# op-synth_0_9.net
KiCad netlist of a schematic drawn in EAGLE
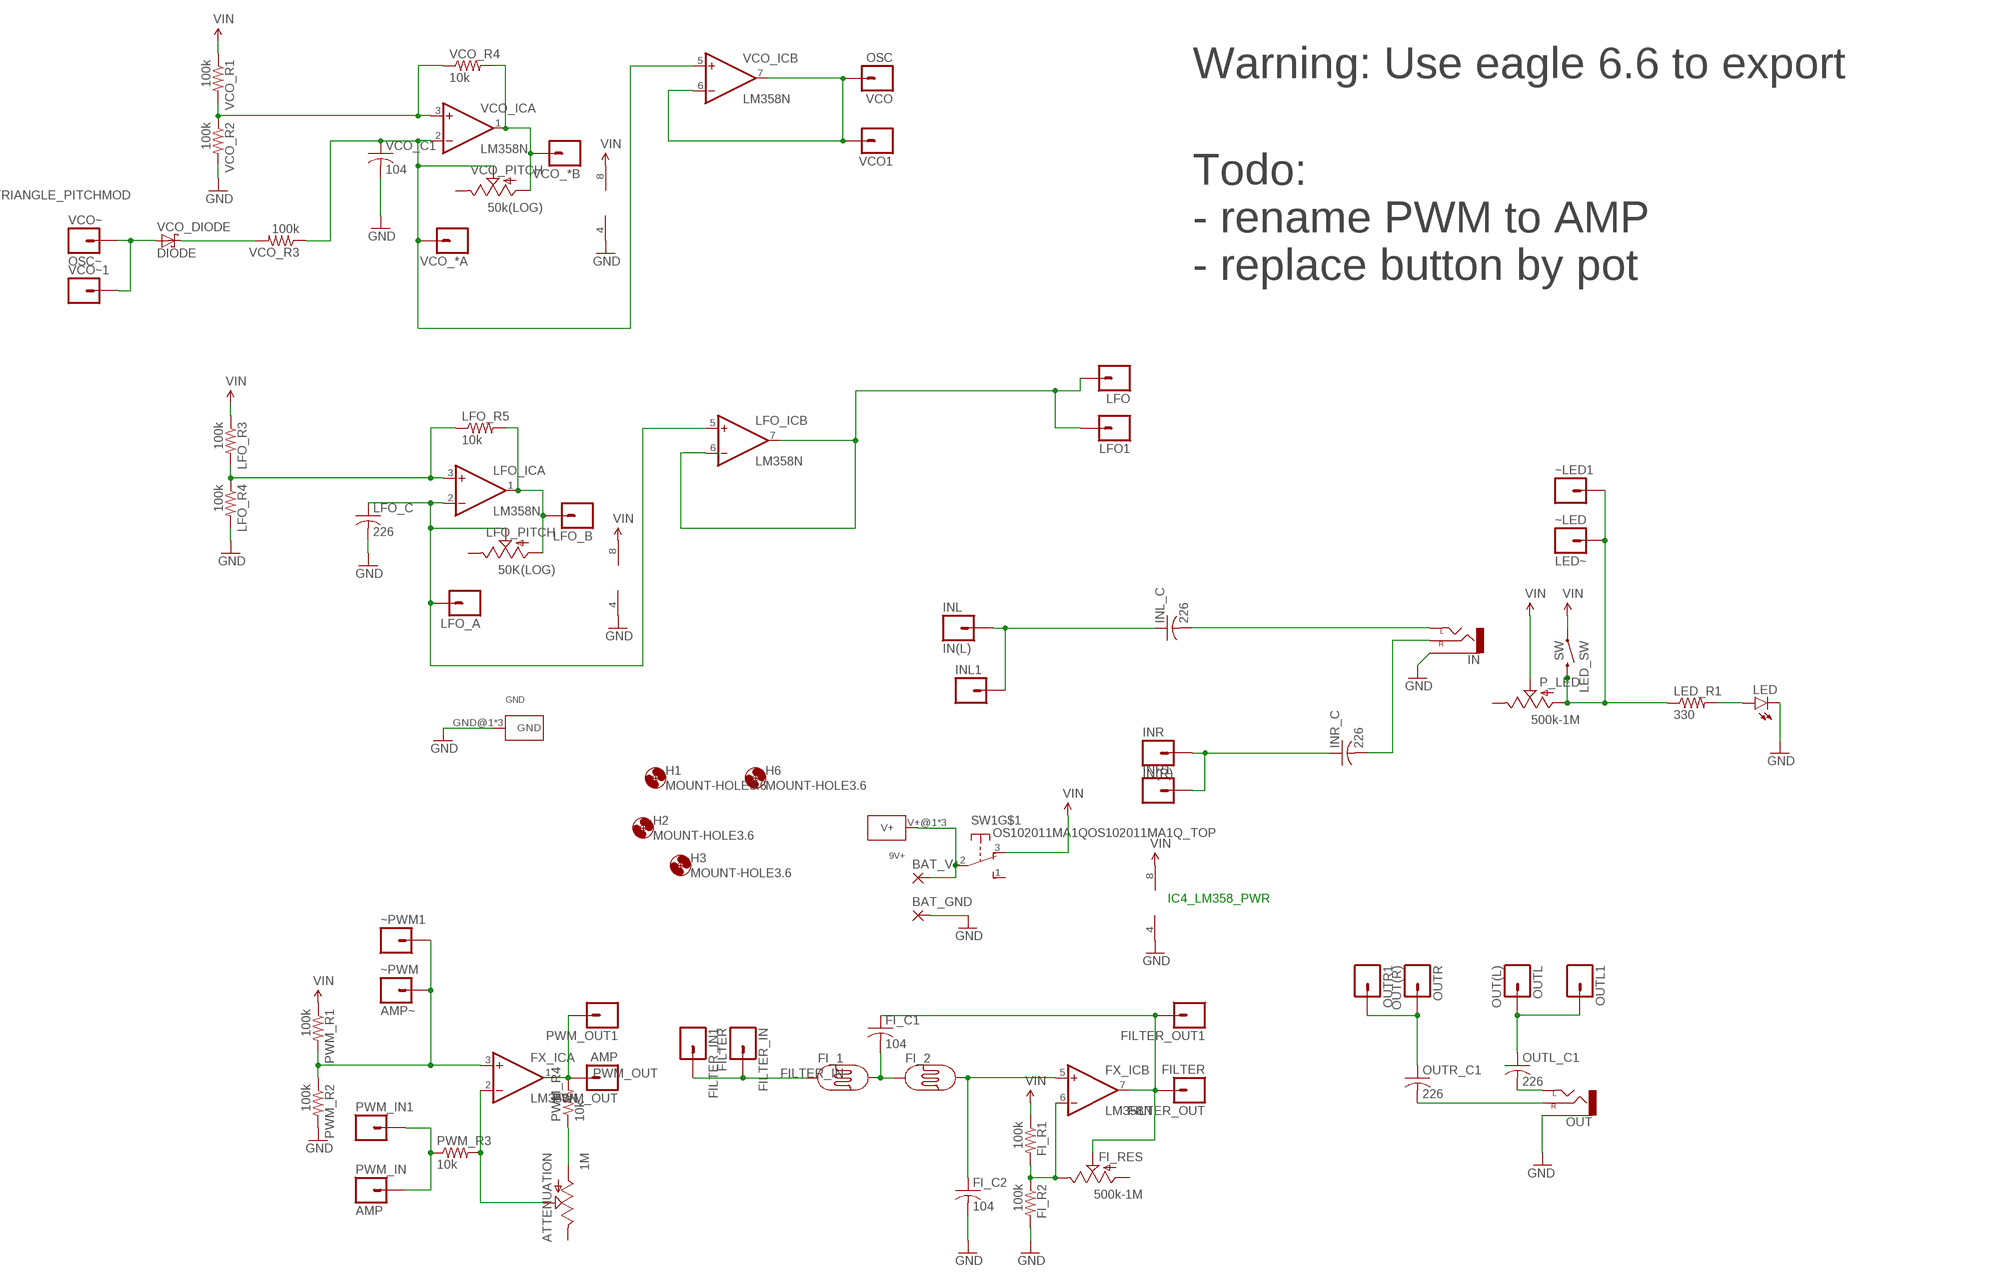
[diagram p0: schematic, sheet 1]

(export (version "E")
  (design (tool "Eeschema 10.0.6"))
  (components
    (comp (ref "9V+")
      (value "KEYSTONE-629+")
      (footprint "eagle-import:KEYSTONE_BATTAERY_TERMINAL-629+")
      (libsource (lib "eagle-import") (part "KEYSTONE-629+"))
    )
    (comp (ref "ATTENUATION")
      (value "1M")
      (footprint "eagle-import:TRIM_POT")
      (libsource (lib "eagle-import") (part "POTTRIM"))
    )
    (comp (ref "BAT_GND")
      (value "3,81/1,4")
      (footprint "eagle-import:3,81_1,4")
      (libsource (lib "eagle-import") (part "3,81/1,4"))
    )
    (comp (ref "BAT_V+")
      (value "3,81/1,4")
      (footprint "eagle-import:3,81_1,4")
      (libsource (lib "eagle-import") (part "3,81/1,4"))
    )
    (comp (ref "FILTER_IN")
      (value "FILTER")
      (footprint "eagle-import:1X01_SIDE_NAME")
      (libsource (lib "eagle-import") (part "HEADER-1X1"))
    )
    (comp (ref "FILTER_IN1")
      (value "HEADER-1X1")
      (footprint "eagle-import:1X01_SIDE_NAME")
      (libsource (lib "eagle-import") (part "HEADER-1X1"))
    )
    (comp (ref "FILTER_OUT")
      (value "FILTER")
      (footprint "eagle-import:1X01_SIDE_NAME")
      (libsource (lib "eagle-import") (part "HEADER-1X1"))
    )
    (comp (ref "FILTER_OUT1")
      (value "HEADER-1X1")
      (footprint "eagle-import:1X01_SIDE_NAME")
      (libsource (lib "eagle-import") (part "HEADER-1X1"))
    )
    (comp (ref "FI_1")
      (value "PHOTOCELLPTH")
      (footprint "eagle-import:PHOTOCELL")
      (libsource (lib "eagle-import") (part "PHOTOCELLPTH"))
    )
    (comp (ref "FI_2")
      (value "PHOTOCELLPTH")
      (footprint "eagle-import:PHOTOCELL")
      (libsource (lib "eagle-import") (part "PHOTOCELLPTH"))
    )
    (comp (ref "FI_C1")
      (value "104")
      (footprint "eagle-import:C050-024X044")
      (libsource (lib "eagle-import") (part "resistor_C-US050-024X044"))
    )
    (comp (ref "FI_C2")
      (value "104")
      (footprint "eagle-import:C050-024X044")
      (libsource (lib "eagle-import") (part "resistor_C-US050-024X044"))
    )
    (comp (ref "FI_R1")
      (value "100k")
      (footprint "eagle-import:0204_7")
      (libsource (lib "eagle-import") (part "R-US_0204/7"))
    )
    (comp (ref "FI_R2")
      (value "100k")
      (footprint "eagle-import:0204_7")
      (libsource (lib "eagle-import") (part "R-US_0204/7"))
    )
    (comp (ref "FI_RES")
      (value "500k-1M")
      (footprint "eagle-import:ALPS_POT")
      (libsource (lib "eagle-import") (part "POT"))
    )
    (comp (ref "FX_IC")
      (value "LM358N")
      (footprint "eagle-import:DIL08")
      (libsource (lib "eagle-import") (part "LM358N"))
    )
    (comp (ref "GND")
      (value "KEYSTONE-629")
      (footprint "eagle-import:KEYSTONE_AA_AAA_BATTERY_TERMINAL-629")
      (libsource (lib "eagle-import") (part "KEYSTONE-629"))
    )
    (comp (ref "H1")
      (value "MOUNT-HOLE3.6")
      (footprint "eagle-import:3,6")
      (libsource (lib "eagle-import") (part "MOUNT-HOLE3.6"))
    )
    (comp (ref "H2")
      (value "MOUNT-HOLE3.6")
      (footprint "eagle-import:3,6")
      (libsource (lib "eagle-import") (part "MOUNT-HOLE3.6"))
    )
    (comp (ref "H3")
      (value "MOUNT-HOLE3.6")
      (footprint "eagle-import:3,6")
      (libsource (lib "eagle-import") (part "MOUNT-HOLE3.6"))
    )
    (comp (ref "H6")
      (value "MOUNT-HOLE3.6")
      (footprint "eagle-import:3,6")
      (libsource (lib "eagle-import") (part "MOUNT-HOLE3.6"))
    )
    (comp (ref "IN")
      (value "AUDIO-JACKPTH")
      (footprint "eagle-import:AUDIO-JACK")
      (libsource (lib "eagle-import") (part "AUDIO-JACKPTH"))
    )
    (comp (ref "INL")
      (value "IN(L)")
      (footprint "eagle-import:1X01_SIDE_NAME")
      (libsource (lib "eagle-import") (part "HEADER-1X1"))
    )
    (comp (ref "INL1")
      (value "HEADER-1X1")
      (footprint "eagle-import:1X01_SIDE_NAME")
      (libsource (lib "eagle-import") (part "HEADER-1X1"))
    )
    (comp (ref "INL_C")
      (value "226")
      (footprint "eagle-import:C050-024X044")
      (libsource (lib "eagle-import") (part "C-US050-024X044"))
    )
    (comp (ref "INR")
      (value "IN(R)")
      (footprint "eagle-import:1X01_SIDE_NAME")
      (libsource (lib "eagle-import") (part "HEADER-1X1"))
    )
    (comp (ref "INR1")
      (value "HEADER-1X1")
      (footprint "eagle-import:1X01_SIDE_NAME")
      (libsource (lib "eagle-import") (part "HEADER-1X1"))
    )
    (comp (ref "INR_C")
      (value "226")
      (footprint "eagle-import:C050-024X044")
      (libsource (lib "eagle-import") (part "C-US050-024X044"))
    )
    (comp (ref "LED")
      (value "LED5MM")
      (footprint "eagle-import:LED5MM")
      (libsource (lib "eagle-import") (part "LED5MM"))
    )
    (comp (ref "LED_R1")
      (value "330")
      (footprint "eagle-import:0204_7")
      (libsource (lib "eagle-import") (part "R-US_0204/7"))
    )
    (comp (ref "LED_SW")
      (value "SW")
      (footprint "eagle-import:TACTILE-PTH-12MM")
      (libsource (lib "eagle-import") (part "SWITCH-MOMENTARY-212MM"))
    )
    (comp (ref "LFO")
      (value "HEADER-1X1")
      (footprint "eagle-import:1X01_SIDE_NAME")
      (libsource (lib "eagle-import") (part "HEADER-1X1"))
    )
    (comp (ref "LFO1")
      (value "HEADER-1X1")
      (footprint "eagle-import:1X01_SIDE_NAME")
      (libsource (lib "eagle-import") (part "HEADER-1X1"))
    )
    (comp (ref "LFO_A")
      (value "HEADER-1X1")
      (footprint "eagle-import:1X01_SIDE_NAME")
      (libsource (lib "eagle-import") (part "HEADER-1X1"))
    )
    (comp (ref "LFO_B")
      (value "HEADER-1X1")
      (footprint "eagle-import:1X01_SIDE_NAME")
      (libsource (lib "eagle-import") (part "HEADER-1X1"))
    )
    (comp (ref "LFO_C")
      (value "226")
      (footprint "eagle-import:C050-024X044")
      (libsource (lib "eagle-import") (part "resistor_C-US050-024X044"))
    )
    (comp (ref "LFO_IC")
      (value "LM358N")
      (footprint "eagle-import:DIL08")
      (libsource (lib "eagle-import") (part "LM358N"))
    )
    (comp (ref "LFO_PITCH")
      (value "50K(LOG)")
      (footprint "eagle-import:ALPS_POT")
      (libsource (lib "eagle-import") (part "POT"))
    )
    (comp (ref "LFO_R3")
      (value "100k")
      (footprint "eagle-import:0204_7")
      (libsource (lib "eagle-import") (part "R-US_0204/7"))
    )
    (comp (ref "LFO_R4")
      (value "100k")
      (footprint "eagle-import:0204_7")
      (libsource (lib "eagle-import") (part "R-US_0204/7"))
    )
    (comp (ref "LFO_R5")
      (value "10k")
      (footprint "eagle-import:0204_7")
      (libsource (lib "eagle-import") (part "R-US_0204/7"))
    )
    (comp (ref "OUT")
      (value "AUDIO-JACKPTH")
      (footprint "eagle-import:AUDIO-JACK")
      (libsource (lib "eagle-import") (part "AUDIO-JACKPTH"))
    )
    (comp (ref "OUTL")
      (value "OUT(L)")
      (footprint "eagle-import:1X01_SIDE_NAME")
      (libsource (lib "eagle-import") (part "HEADER-1X1"))
    )
    (comp (ref "OUTL1")
      (value "HEADER-1X1")
      (footprint "eagle-import:1X01_SIDE_NAME")
      (libsource (lib "eagle-import") (part "HEADER-1X1"))
    )
    (comp (ref "OUTL_C1")
      (value "226")
      (footprint "eagle-import:C050-024X044")
      (libsource (lib "eagle-import") (part "C-US050-024X044"))
    )
    (comp (ref "OUTR")
      (value "OUT(R)")
      (footprint "eagle-import:1X01_SIDE_NAME")
      (libsource (lib "eagle-import") (part "HEADER-1X1"))
    )
    (comp (ref "OUTR1")
      (value "HEADER-1X1")
      (footprint "eagle-import:1X01_SIDE_NAME")
      (libsource (lib "eagle-import") (part "HEADER-1X1"))
    )
    (comp (ref "OUTR_C1")
      (value "226")
      (footprint "eagle-import:C050-024X044")
      (libsource (lib "eagle-import") (part "C-US050-024X044"))
    )
    (comp (ref "PWM_IN")
      (value "AMP")
      (footprint "eagle-import:1X01_SIDE_NAME")
      (libsource (lib "eagle-import") (part "HEADER-1X1"))
    )
    (comp (ref "PWM_IN1")
      (value "HEADER-1X1")
      (footprint "eagle-import:1X01_SIDE_NAME")
      (libsource (lib "eagle-import") (part "HEADER-1X1"))
    )
    (comp (ref "PWM_OUT")
      (value "AMP")
      (footprint "eagle-import:1X01_SIDE_NAME")
      (libsource (lib "eagle-import") (part "HEADER-1X1"))
    )
    (comp (ref "PWM_OUT1")
      (value "HEADER-1X1")
      (footprint "eagle-import:1X01_SIDE_NAME")
      (libsource (lib "eagle-import") (part "HEADER-1X1"))
    )
    (comp (ref "PWM_R1")
      (value "100k")
      (footprint "eagle-import:0204_7")
      (libsource (lib "eagle-import") (part "R-US_0204/7"))
    )
    (comp (ref "PWM_R2")
      (value "100k")
      (footprint "eagle-import:0204_7")
      (libsource (lib "eagle-import") (part "R-US_0204/7"))
    )
    (comp (ref "PWM_R3")
      (value "10k")
      (footprint "eagle-import:0204_7")
      (libsource (lib "eagle-import") (part "R-US_0204/7"))
    )
    (comp (ref "PWM_R4")
      (value "10k")
      (footprint "eagle-import:0204_7")
      (libsource (lib "eagle-import") (part "R-US_0204/7"))
    )
    (comp (ref "P_LED")
      (value "500k-1M")
      (footprint "eagle-import:ALPS_POT")
      (libsource (lib "eagle-import") (part "POT"))
    )
    (comp (ref "SW1")
      (value "OS102011MA1QOS102011MA1Q_TOP")
      (footprint "eagle-import:OS102011MA1Q")
      (libsource (lib "eagle-import") (part "OS102011MA1QOS102011MA1Q_TOP"))
    )
    (comp (ref "VCO")
      (value "OSC")
      (footprint "eagle-import:1X01_SIDE_NAME")
      (libsource (lib "eagle-import") (part "HEADER-1X1"))
    )
    (comp (ref "VCO1")
      (value "HEADER-1X1")
      (footprint "eagle-import:1X01_SIDE_NAME")
      (libsource (lib "eagle-import") (part "HEADER-1X1"))
    )
    (comp (ref "VCO_*A")
      (value "HEADER-1X1")
      (footprint "eagle-import:1X01_SIDE_NAME")
      (libsource (lib "eagle-import") (part "HEADER-1X1"))
    )
    (comp (ref "VCO_*B")
      (value "HEADER-1X1")
      (footprint "eagle-import:1X01_SIDE_NAME")
      (libsource (lib "eagle-import") (part "HEADER-1X1"))
    )
    (comp (ref "VCO_C1")
      (value "104")
      (footprint "eagle-import:C050-024X044")
      (libsource (lib "eagle-import") (part "C-US050-024X044"))
    )
    (comp (ref "VCO_DIODE")
      (value "DIODE")
      (footprint "eagle-import:DO41-7")
      (libsource (lib "eagle-import") (part "SCHOTTKY-DIODEDO41-7"))
    )
    (comp (ref "VCO_IC")
      (value "LM358N")
      (footprint "eagle-import:DIL08")
      (libsource (lib "eagle-import") (part "LM358N"))
    )
    (comp (ref "VCO_PITCH")
      (value "50k(LOG)")
      (footprint "eagle-import:ALPS_POT")
      (libsource (lib "eagle-import") (part "POT"))
    )
    (comp (ref "VCO_R1")
      (value "100k")
      (footprint "eagle-import:0204_7")
      (libsource (lib "eagle-import") (part "R-US_0204/7"))
    )
    (comp (ref "VCO_R2")
      (value "100k")
      (footprint "eagle-import:0204_7")
      (libsource (lib "eagle-import") (part "R-US_0204/7"))
    )
    (comp (ref "VCO_R3")
      (value "100k")
      (footprint "eagle-import:0204_7")
      (libsource (lib "eagle-import") (part "R-US_0204/7"))
    )
    (comp (ref "VCO_R4")
      (value "10k")
      (footprint "eagle-import:0204_7")
      (libsource (lib "eagle-import") (part "R-US_0204/7"))
    )
    (comp (ref "VCO~")
      (value "OSC~")
      (footprint "eagle-import:1X01_SIDE_NAME")
      (libsource (lib "eagle-import") (part "HEADER-1X1"))
    )
    (comp (ref "VCO~1")
      (value "HEADER-1X1")
      (footprint "eagle-import:1X01_SIDE_NAME")
      (libsource (lib "eagle-import") (part "HEADER-1X1"))
    )
    (comp (ref "~LED")
      (value "LED~")
      (footprint "eagle-import:1X01_SIDE_NAME")
      (libsource (lib "eagle-import") (part "HEADER-1X1"))
    )
    (comp (ref "~LED1")
      (value "HEADER-1X1")
      (footprint "eagle-import:1X01_SIDE_NAME")
      (libsource (lib "eagle-import") (part "HEADER-1X1"))
    )
    (comp (ref "~PWM")
      (value "AMP~")
      (footprint "eagle-import:1X01_SIDE_NAME")
      (libsource (lib "eagle-import") (part "HEADER-1X1"))
    )
    (comp (ref "~PWM1")
      (value "HEADER-1X1")
      (footprint "eagle-import:1X01_SIDE_NAME")
      (libsource (lib "eagle-import") (part "HEADER-1X1"))
    )
  )
  (nets
    (net (code "1") (name "/FILTER_IN") (class "Default")
      (node (ref "FILTER_IN") (pin "1") (pinfunction "1_1") (pintype "passive"))
      (node (ref "FILTER_IN1") (pin "1") (pinfunction "1_1") (pintype "passive"))
      (node (ref "FI_1") (pin "1") (pinfunction "P$1_1") (pintype "bidirectional"))
    )
    (net (code "2") (name "/PWM_OUT") (class "Default")
      (node (ref "FX_IC") (pin "1") (pinfunction "OUT_1") (pintype "output"))
      (node (ref "PWM_OUT") (pin "1") (pinfunction "1_1") (pintype "passive"))
      (node (ref "PWM_OUT1") (pin "1") (pinfunction "1_1") (pintype "passive"))
      (node (ref "PWM_R4") (pin "2") (pinfunction "2_2") (pintype "passive"))
    )
    (net (code "3") (name "/TRIANGLE_PITCHMOD") (class "Default")
      (node (ref "VCO_DIODE") (pin "A") (pinfunction "A_A") (pintype "passive"))
      (node (ref "VCO~") (pin "1") (pinfunction "1_1") (pintype "passive"))
      (node (ref "VCO~1") (pin "1") (pinfunction "1_1") (pintype "passive"))
    )
    (net (code "4") (name "GND") (class "Default")
      (node (ref "BAT_GND") (pin "1") (pinfunction "P_1") (pintype "passive"))
      (node (ref "FI_C2") (pin "2") (pinfunction "2_2") (pintype "passive"))
      (node (ref "FI_R2") (pin "2") (pinfunction "2_2") (pintype "passive"))
      (node (ref "FX_IC") (pin "4") (pinfunction "V-_4") (pintype "power_in"))
      (node (ref "GND") (pin "GND@1") (pinfunction "GND_GND@1") (pintype "power_in"))
      (node (ref "GND") (pin "GND@2") (pinfunction "GND_GND@2") (pintype "power_in"))
      (node (ref "GND") (pin "GND@3") (pinfunction "GND_GND@3") (pintype "power_in"))
      (node (ref "IN") (pin "SLEEVE") (pinfunction "SLEEVE_SLEEVE") (pintype "bidirectional"))
      (node (ref "LED") (pin "K") (pinfunction "C_K") (pintype "passive"))
      (node (ref "LFO_C") (pin "2") (pinfunction "2_2") (pintype "passive"))
      (node (ref "LFO_IC") (pin "4") (pinfunction "V-_4") (pintype "power_in"))
      (node (ref "LFO_R4") (pin "2") (pinfunction "2_2") (pintype "passive"))
      (node (ref "OUT") (pin "SLEEVE") (pinfunction "SLEEVE_SLEEVE") (pintype "bidirectional"))
      (node (ref "PWM_R2") (pin "2") (pinfunction "2_2") (pintype "passive"))
      (node (ref "VCO_C1") (pin "2") (pinfunction "2_2") (pintype "passive"))
      (node (ref "VCO_IC") (pin "4") (pinfunction "V-_4") (pintype "power_in"))
      (node (ref "VCO_R2") (pin "2") (pinfunction "2_2") (pintype "passive"))
    )
    (net (code "5") (name "Net-(ATTENUATION-A)") (class "Default")
      (node (ref "ATTENUATION") (pin "3") (pinfunction "A_3") (pintype "passive"))
      (node (ref "PWM_R4") (pin "1") (pinfunction "1_1") (pintype "passive"))
    )
    (net (code "6") (name "Net-(ATTENUATION-S)") (class "Default")
      (node (ref "ATTENUATION") (pin "1") (pinfunction "S_1") (pintype "passive"))
      (node (ref "FX_IC") (pin "2") (pinfunction "-IN_2") (pintype "input"))
      (node (ref "PWM_R3") (pin "2") (pinfunction "2_2") (pintype "passive"))
    )
    (net (code "7") (name "Net-(BAT_V+-P)") (class "Default")
      (node (ref "9V+") (pin "V+@1") (pinfunction "V+_V+@1") (pintype "power_in"))
      (node (ref "9V+") (pin "V+@2") (pinfunction "V+_V+@2") (pintype "power_in"))
      (node (ref "9V+") (pin "V+@3") (pinfunction "V+_V+@3") (pintype "power_in"))
      (node (ref "BAT_V+") (pin "1") (pinfunction "P_1") (pintype "passive"))
      (node (ref "SW1") (pin "2") (pinfunction "P_2") (pintype "passive"))
    )
    (net (code "8") (name "Net-(FI_1-P$2)") (class "Default")
      (node (ref "FI_1") (pin "2") (pinfunction "P$2_2") (pintype "bidirectional"))
      (node (ref "FI_2") (pin "1") (pinfunction "P$1_1") (pintype "bidirectional"))
      (node (ref "FI_C1") (pin "2") (pinfunction "2_2") (pintype "passive"))
    )
    (net (code "9") (name "Net-(FI_2-P$2)") (class "Default")
      (node (ref "FI_2") (pin "2") (pinfunction "P$2_2") (pintype "bidirectional"))
      (node (ref "FI_C2") (pin "1") (pinfunction "1_1") (pintype "passive"))
      (node (ref "FX_IC") (pin "5") (pinfunction "+IN_5") (pintype "input"))
    )
    (net (code "10") (name "Net-(FI_RES-E)") (class "Default")
      (node (ref "FI_R1") (pin "2") (pinfunction "2_2") (pintype "passive"))
      (node (ref "FI_R2") (pin "1") (pinfunction "1_1") (pintype "passive"))
      (node (ref "FI_RES") (pin "P$1") (pinfunction "E_P$1") (pintype "passive"))
      (node (ref "FX_IC") (pin "6") (pinfunction "-IN_6") (pintype "input"))
    )
    (net (code "11") (name "Net-(FI_RES-S)") (class "Default")
      (node (ref "FILTER_OUT") (pin "1") (pinfunction "1_1") (pintype "passive"))
      (node (ref "FILTER_OUT1") (pin "1") (pinfunction "1_1") (pintype "passive"))
      (node (ref "FI_C1") (pin "1") (pinfunction "1_1") (pintype "passive"))
      (node (ref "FI_RES") (pin "P$2") (pinfunction "S_P$2") (pintype "passive"))
      (node (ref "FX_IC") (pin "7") (pinfunction "OUT_7") (pintype "output"))
    )
    (net (code "12") (name "Net-(FX_ICA-+IN)") (class "Default")
      (node (ref "FX_IC") (pin "3") (pinfunction "+IN_3") (pintype "input"))
      (node (ref "PWM_R1") (pin "2") (pinfunction "2_2") (pintype "passive"))
      (node (ref "PWM_R2") (pin "1") (pinfunction "1_1") (pintype "passive"))
      (node (ref "~PWM") (pin "1") (pinfunction "1_1") (pintype "passive"))
      (node (ref "~PWM1") (pin "1") (pinfunction "1_1") (pintype "passive"))
    )
    (net (code "13") (name "Net-(IN-LEFT)") (class "Default")
      (node (ref "IN") (pin "TIP") (pinfunction "LEFT_TIP") (pintype "bidirectional"))
      (node (ref "INL_C") (pin "2") (pinfunction "2_2") (pintype "passive"))
    )
    (net (code "14") (name "Net-(IN-RIGHT)") (class "Default")
      (node (ref "IN") (pin "RING") (pinfunction "RIGHT_RING") (pintype "bidirectional"))
      (node (ref "INR_C") (pin "2") (pinfunction "2_2") (pintype "passive"))
    )
    (net (code "15") (name "Net-(INL-Pad1)") (class "Default")
      (node (ref "INL") (pin "1") (pinfunction "1_1") (pintype "passive"))
      (node (ref "INL1") (pin "1") (pinfunction "1_1") (pintype "passive"))
      (node (ref "INL_C") (pin "1") (pinfunction "1_1") (pintype "passive"))
    )
    (net (code "16") (name "Net-(INR-Pad1)") (class "Default")
      (node (ref "INR") (pin "1") (pinfunction "1_1") (pintype "passive"))
      (node (ref "INR1") (pin "1") (pinfunction "1_1") (pintype "passive"))
      (node (ref "INR_C") (pin "1") (pinfunction "1_1") (pintype "passive"))
    )
    (net (code "17") (name "Net-(LED-PadA)") (class "Default")
      (node (ref "LED") (pin "A") (pinfunction "A_A") (pintype "passive"))
      (node (ref "LED_R1") (pin "2") (pinfunction "2_2") (pintype "passive"))
    )
    (net (code "18") (name "Net-(LED_SW-2)") (class "Default")
      (node (ref "LED_R1") (pin "1") (pinfunction "1_1") (pintype "passive"))
      (node (ref "LED_SW") (pin "3") (pinfunction "2_3") (pintype "passive"))
      (node (ref "P_LED") (pin "P$3") (pinfunction "A_P$3") (pintype "passive"))
      (node (ref "~LED") (pin "1") (pinfunction "1_1") (pintype "passive"))
      (node (ref "~LED1") (pin "1") (pinfunction "1_1") (pintype "passive"))
    )
    (net (code "19") (name "Net-(LFO_ICA-+IN)") (class "Default")
      (node (ref "LFO_IC") (pin "3") (pinfunction "+IN_3") (pintype "input"))
      (node (ref "LFO_R3") (pin "2") (pinfunction "2_2") (pintype "passive"))
      (node (ref "LFO_R4") (pin "1") (pinfunction "1_1") (pintype "passive"))
      (node (ref "LFO_R5") (pin "1") (pinfunction "1_1") (pintype "passive"))
    )
    (net (code "20") (name "Net-(LFO_ICA--IN)") (class "Default")
      (node (ref "LFO_A") (pin "1") (pinfunction "1_1") (pintype "passive"))
      (node (ref "LFO_C") (pin "1") (pinfunction "1_1") (pintype "passive"))
      (node (ref "LFO_IC") (pin "2") (pinfunction "-IN_2") (pintype "input"))
      (node (ref "LFO_IC") (pin "5") (pinfunction "+IN_5") (pintype "input"))
      (node (ref "LFO_PITCH") (pin "P$2") (pinfunction "S_P$2") (pintype "passive"))
    )
    (net (code "21") (name "Net-(LFO_ICA-OUT)") (class "Default")
      (node (ref "LFO_B") (pin "1") (pinfunction "1_1") (pintype "passive"))
      (node (ref "LFO_IC") (pin "1") (pinfunction "OUT_1") (pintype "output"))
      (node (ref "LFO_PITCH") (pin "P$3") (pinfunction "A_P$3") (pintype "passive"))
      (node (ref "LFO_R5") (pin "2") (pinfunction "2_2") (pintype "passive"))
    )
    (net (code "22") (name "Net-(LFO_ICB--IN)") (class "Default")
      (node (ref "LFO") (pin "1") (pinfunction "1_1") (pintype "passive"))
      (node (ref "LFO1") (pin "1") (pinfunction "1_1") (pintype "passive"))
      (node (ref "LFO_IC") (pin "6") (pinfunction "-IN_6") (pintype "input"))
      (node (ref "LFO_IC") (pin "7") (pinfunction "OUT_7") (pintype "output"))
    )
    (net (code "23") (name "Net-(OUT-LEFT)") (class "Default")
      (node (ref "OUT") (pin "TIP") (pinfunction "LEFT_TIP") (pintype "bidirectional"))
      (node (ref "OUTL_C1") (pin "2") (pinfunction "2_2") (pintype "passive"))
    )
    (net (code "24") (name "Net-(OUT-RIGHT)") (class "Default")
      (node (ref "OUT") (pin "RING") (pinfunction "RIGHT_RING") (pintype "bidirectional"))
      (node (ref "OUTR_C1") (pin "2") (pinfunction "2_2") (pintype "passive"))
    )
    (net (code "25") (name "Net-(OUTL-Pad1)") (class "Default")
      (node (ref "OUTL") (pin "1") (pinfunction "1_1") (pintype "passive"))
      (node (ref "OUTL1") (pin "1") (pinfunction "1_1") (pintype "passive"))
      (node (ref "OUTL_C1") (pin "1") (pinfunction "1_1") (pintype "passive"))
    )
    (net (code "26") (name "Net-(OUTR-Pad1)") (class "Default")
      (node (ref "OUTR") (pin "1") (pinfunction "1_1") (pintype "passive"))
      (node (ref "OUTR1") (pin "1") (pinfunction "1_1") (pintype "passive"))
      (node (ref "OUTR_C1") (pin "1") (pinfunction "1_1") (pintype "passive"))
    )
    (net (code "27") (name "Net-(PWM_IN-Pad1)") (class "Default")
      (node (ref "PWM_IN") (pin "1") (pinfunction "1_1") (pintype "passive"))
      (node (ref "PWM_IN1") (pin "1") (pinfunction "1_1") (pintype "passive"))
      (node (ref "PWM_R3") (pin "1") (pinfunction "1_1") (pintype "passive"))
    )
    (net (code "28") (name "Net-(VCO_DIODE-PadC)") (class "Default")
      (node (ref "VCO_DIODE") (pin "C") (pinfunction "C_C") (pintype "passive"))
      (node (ref "VCO_R3") (pin "2") (pinfunction "2_2") (pintype "passive"))
    )
    (net (code "29") (name "Net-(VCO_ICA-+IN)") (class "Default")
      (node (ref "VCO_IC") (pin "3") (pinfunction "+IN_3") (pintype "input"))
      (node (ref "VCO_R1") (pin "2") (pinfunction "2_2") (pintype "passive"))
      (node (ref "VCO_R2") (pin "1") (pinfunction "1_1") (pintype "passive"))
      (node (ref "VCO_R4") (pin "1") (pinfunction "1_1") (pintype "passive"))
    )
    (net (code "30") (name "Net-(VCO_ICA--IN)") (class "Default")
      (node (ref "VCO_*A") (pin "1") (pinfunction "1_1") (pintype "passive"))
      (node (ref "VCO_C1") (pin "1") (pinfunction "1_1") (pintype "passive"))
      (node (ref "VCO_IC") (pin "2") (pinfunction "-IN_2") (pintype "input"))
      (node (ref "VCO_IC") (pin "5") (pinfunction "+IN_5") (pintype "input"))
      (node (ref "VCO_PITCH") (pin "P$2") (pinfunction "S_P$2") (pintype "passive"))
      (node (ref "VCO_R3") (pin "1") (pinfunction "1_1") (pintype "passive"))
    )
    (net (code "31") (name "Net-(VCO_ICA-OUT)") (class "Default")
      (node (ref "VCO_*B") (pin "1") (pinfunction "1_1") (pintype "passive"))
      (node (ref "VCO_IC") (pin "1") (pinfunction "OUT_1") (pintype "output"))
      (node (ref "VCO_PITCH") (pin "P$3") (pinfunction "A_P$3") (pintype "passive"))
      (node (ref "VCO_R4") (pin "2") (pinfunction "2_2") (pintype "passive"))
    )
    (net (code "32") (name "Net-(VCO_ICB--IN)") (class "Default")
      (node (ref "VCO") (pin "1") (pinfunction "1_1") (pintype "passive"))
      (node (ref "VCO1") (pin "1") (pinfunction "1_1") (pintype "passive"))
      (node (ref "VCO_IC") (pin "6") (pinfunction "-IN_6") (pintype "input"))
      (node (ref "VCO_IC") (pin "7") (pinfunction "OUT_7") (pintype "output"))
    )
    (net (code "33") (name "VIN") (class "Default")
      (node (ref "FI_R1") (pin "1") (pinfunction "1_1") (pintype "passive"))
      (node (ref "FX_IC") (pin "8") (pinfunction "V+_8") (pintype "power_in"))
      (node (ref "LED_SW") (pin "1") (pinfunction "1_1") (pintype "passive"))
      (node (ref "LFO_IC") (pin "8") (pinfunction "V+_8") (pintype "power_in"))
      (node (ref "LFO_R3") (pin "1") (pinfunction "1_1") (pintype "passive"))
      (node (ref "PWM_R1") (pin "1") (pinfunction "1_1") (pintype "passive"))
      (node (ref "P_LED") (pin "P$2") (pinfunction "S_P$2") (pintype "passive"))
      (node (ref "SW1") (pin "3") (pinfunction "O_3") (pintype "passive"))
      (node (ref "VCO_IC") (pin "8") (pinfunction "V+_8") (pintype "power_in"))
      (node (ref "VCO_R1") (pin "1") (pinfunction "1_1") (pintype "passive"))
    )
    (net (code "34") (name "unconnected-(ATTENUATION-E-Pad2)") (class "Default")
      (node (ref "ATTENUATION") (pin "2") (pinfunction "E_2") (pintype "passive"))
    )
    (net (code "35") (name "unconnected-(FI_RES-A-PadP$3)") (class "Default")
      (node (ref "FI_RES") (pin "P$3") (pinfunction "A_P$3") (pintype "passive"))
    )
    (net (code "36") (name "unconnected-(LFO_PITCH-E-PadP$1)") (class "Default")
      (node (ref "LFO_PITCH") (pin "P$1") (pinfunction "E_P$1") (pintype "passive"))
    )
    (net (code "37") (name "unconnected-(P_LED-E-PadP$1)") (class "Default")
      (node (ref "P_LED") (pin "P$1") (pinfunction "E_P$1") (pintype "passive"))
    )
    (net (code "38") (name "unconnected-(SW1A-S-Pad1)") (class "Default")
      (node (ref "SW1") (pin "1") (pinfunction "S_1") (pintype "passive"))
    )
    (net (code "39") (name "unconnected-(VCO_PITCH-E-PadP$1)") (class "Default")
      (node (ref "VCO_PITCH") (pin "P$1") (pinfunction "E_P$1") (pintype "passive"))
    )
  )
)
